# Midi2CV.net
KiCad netlist of a schematic drawn in EAGLE
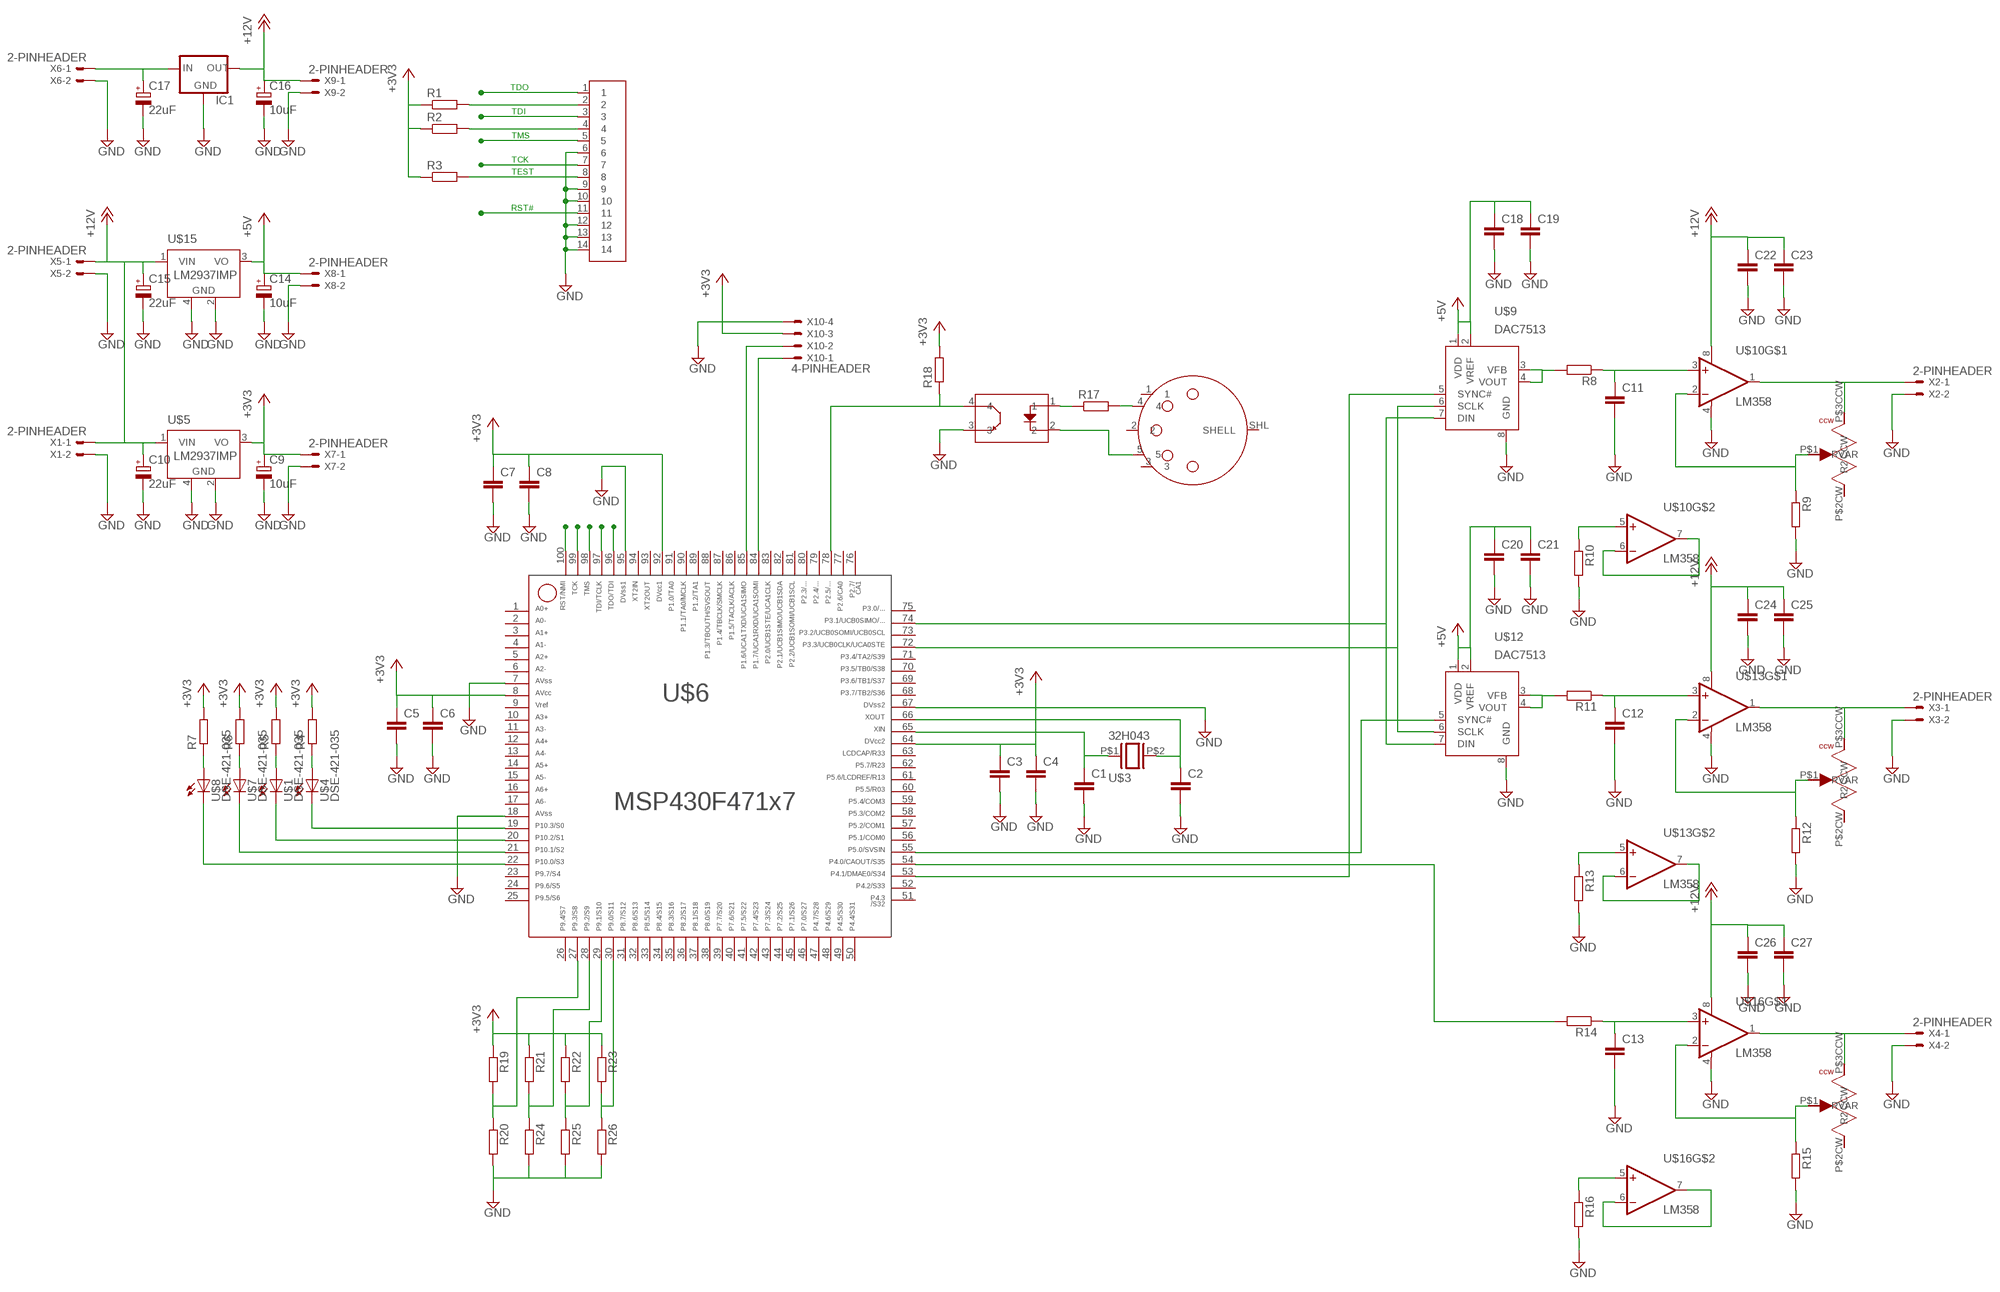
[diagram p0: schematic, sheet 1]

(export (version "E")
  (design (tool "Eeschema 10.0.6"))
  (components
    (comp (ref "C1")
      (value "C-EUC0402")
      (footprint "eagle-import:C0402")
      (libsource (lib "eagle-import") (part "C-EUC0402"))
    )
    (comp (ref "C2")
      (value "C-EUC0402")
      (footprint "eagle-import:C0402")
      (libsource (lib "eagle-import") (part "C-EUC0402"))
    )
    (comp (ref "C3")
      (value "C-EUC0402")
      (footprint "eagle-import:C0402")
      (libsource (lib "eagle-import") (part "C-EUC0402"))
    )
    (comp (ref "C4")
      (value "C-EUC0402")
      (footprint "eagle-import:C0402")
      (libsource (lib "eagle-import") (part "C-EUC0402"))
    )
    (comp (ref "C5")
      (value "C-EUC0402")
      (footprint "eagle-import:C0402")
      (libsource (lib "eagle-import") (part "C-EUC0402"))
    )
    (comp (ref "C6")
      (value "C-EUC0402")
      (footprint "eagle-import:C0402")
      (libsource (lib "eagle-import") (part "C-EUC0402"))
    )
    (comp (ref "C7")
      (value "C-EUC0402")
      (footprint "eagle-import:C0402")
      (libsource (lib "eagle-import") (part "C-EUC0402"))
    )
    (comp (ref "C8")
      (value "C-EUC0402")
      (footprint "eagle-import:C0402")
      (libsource (lib "eagle-import") (part "C-EUC0402"))
    )
    (comp (ref "C9")
      (value "10uF")
      (footprint "eagle-import:SMC_C")
      (libsource (lib "eagle-import") (part "CPOL-EUSMCC"))
    )
    (comp (ref "C10")
      (value "22uF")
      (footprint "eagle-import:SMC_D")
      (libsource (lib "eagle-import") (part "CPOL-EUSMCD"))
    )
    (comp (ref "C11")
      (value "C-EUC0402")
      (footprint "eagle-import:C0402")
      (libsource (lib "eagle-import") (part "C-EUC0402"))
    )
    (comp (ref "C12")
      (value "C-EUC0402")
      (footprint "eagle-import:C0402")
      (libsource (lib "eagle-import") (part "C-EUC0402"))
    )
    (comp (ref "C13")
      (value "C-EUC0402")
      (footprint "eagle-import:C0402")
      (libsource (lib "eagle-import") (part "C-EUC0402"))
    )
    (comp (ref "C14")
      (value "10uF")
      (footprint "eagle-import:SMC_C")
      (libsource (lib "eagle-import") (part "CPOL-EUSMCC"))
    )
    (comp (ref "C15")
      (value "22uF")
      (footprint "eagle-import:SMC_D")
      (libsource (lib "eagle-import") (part "CPOL-EUSMCD"))
    )
    (comp (ref "C16")
      (value "10uF")
      (footprint "eagle-import:SMC_C")
      (libsource (lib "eagle-import") (part "CPOL-EUSMCC"))
    )
    (comp (ref "C17")
      (value "22uF")
      (footprint "eagle-import:SMC_D")
      (libsource (lib "eagle-import") (part "CPOL-EUSMCD"))
    )
    (comp (ref "C18")
      (value "C-EUC0402")
      (footprint "eagle-import:C0402")
      (libsource (lib "eagle-import") (part "C-EUC0402"))
    )
    (comp (ref "C19")
      (value "C-EUC0402")
      (footprint "eagle-import:C0402")
      (libsource (lib "eagle-import") (part "C-EUC0402"))
    )
    (comp (ref "C20")
      (value "C-EUC0402")
      (footprint "eagle-import:C0402")
      (libsource (lib "eagle-import") (part "C-EUC0402"))
    )
    (comp (ref "C21")
      (value "C-EUC0402")
      (footprint "eagle-import:C0402")
      (libsource (lib "eagle-import") (part "C-EUC0402"))
    )
    (comp (ref "C22")
      (value "C-EUC0402")
      (footprint "eagle-import:C0402")
      (libsource (lib "eagle-import") (part "C-EUC0402"))
    )
    (comp (ref "C23")
      (value "C-EUC0402")
      (footprint "eagle-import:C0402")
      (libsource (lib "eagle-import") (part "C-EUC0402"))
    )
    (comp (ref "C24")
      (value "C-EUC0402")
      (footprint "eagle-import:C0402")
      (libsource (lib "eagle-import") (part "C-EUC0402"))
    )
    (comp (ref "C25")
      (value "C-EUC0402")
      (footprint "eagle-import:C0402")
      (libsource (lib "eagle-import") (part "C-EUC0402"))
    )
    (comp (ref "C26")
      (value "C-EUC0402")
      (footprint "eagle-import:C0402")
      (libsource (lib "eagle-import") (part "C-EUC0402"))
    )
    (comp (ref "C27")
      (value "C-EUC0402")
      (footprint "eagle-import:C0402")
      (libsource (lib "eagle-import") (part "C-EUC0402"))
    )
    (comp (ref "IC1")
      (value "78MXXS")
      (footprint "eagle-import:78MXXS")
      (libsource (lib "eagle-import") (part "78MXXS"))
    )
    (comp (ref "R1")
      (value "R-EU_R0402")
      (footprint "eagle-import:R0402")
      (libsource (lib "eagle-import") (part "R-EU_R0402"))
    )
    (comp (ref "R2")
      (value "R-EU_R0402")
      (footprint "eagle-import:R0402")
      (libsource (lib "eagle-import") (part "R-EU_R0402"))
    )
    (comp (ref "R3")
      (value "R-EU_R0402")
      (footprint "eagle-import:R0402")
      (libsource (lib "eagle-import") (part "R-EU_R0402"))
    )
    (comp (ref "R4")
      (value "R-EU_R0402")
      (footprint "eagle-import:R0402")
      (libsource (lib "eagle-import") (part "R-EU_R0402"))
    )
    (comp (ref "R5")
      (value "R-EU_R0402")
      (footprint "eagle-import:R0402")
      (libsource (lib "eagle-import") (part "R-EU_R0402"))
    )
    (comp (ref "R6")
      (value "R-EU_R0402")
      (footprint "eagle-import:R0402")
      (libsource (lib "eagle-import") (part "R-EU_R0402"))
    )
    (comp (ref "R7")
      (value "R-EU_R0402")
      (footprint "eagle-import:R0402")
      (libsource (lib "eagle-import") (part "R-EU_R0402"))
    )
    (comp (ref "R8")
      (value "R-EU_R0402")
      (footprint "eagle-import:R0402")
      (libsource (lib "eagle-import") (part "R-EU_R0402"))
    )
    (comp (ref "R9")
      (value "R-EU_R0402")
      (footprint "eagle-import:R0402")
      (libsource (lib "eagle-import") (part "R-EU_R0402"))
    )
    (comp (ref "R10")
      (value "R-EU_R0402")
      (footprint "eagle-import:R0402")
      (libsource (lib "eagle-import") (part "R-EU_R0402"))
    )
    (comp (ref "R11")
      (value "R-EU_R0402")
      (footprint "eagle-import:R0402")
      (libsource (lib "eagle-import") (part "R-EU_R0402"))
    )
    (comp (ref "R12")
      (value "R-EU_R0402")
      (footprint "eagle-import:R0402")
      (libsource (lib "eagle-import") (part "R-EU_R0402"))
    )
    (comp (ref "R13")
      (value "R-EU_R0402")
      (footprint "eagle-import:R0402")
      (libsource (lib "eagle-import") (part "R-EU_R0402"))
    )
    (comp (ref "R14")
      (value "R-EU_R0402")
      (footprint "eagle-import:R0402")
      (libsource (lib "eagle-import") (part "R-EU_R0402"))
    )
    (comp (ref "R15")
      (value "R-EU_R0402")
      (footprint "eagle-import:R0402")
      (libsource (lib "eagle-import") (part "R-EU_R0402"))
    )
    (comp (ref "R16")
      (value "R-EU_R0402")
      (footprint "eagle-import:R0402")
      (libsource (lib "eagle-import") (part "R-EU_R0402"))
    )
    (comp (ref "R17")
      (value "R-EU_R1206")
      (footprint "eagle-import:R1206")
      (libsource (lib "eagle-import") (part "R-EU_R1206"))
    )
    (comp (ref "R18")
      (value "R-EU_R1206")
      (footprint "eagle-import:R1206")
      (libsource (lib "eagle-import") (part "R-EU_R1206"))
    )
    (comp (ref "R19")
      (value "R-EU_R0402")
      (footprint "eagle-import:R0402")
      (libsource (lib "eagle-import") (part "R-EU_R0402"))
    )
    (comp (ref "R20")
      (value "R-EU_R0402")
      (footprint "eagle-import:R0402")
      (libsource (lib "eagle-import") (part "R-EU_R0402"))
    )
    (comp (ref "R21")
      (value "R-EU_R0402")
      (footprint "eagle-import:R0402")
      (libsource (lib "eagle-import") (part "R-EU_R0402"))
    )
    (comp (ref "R22")
      (value "R-EU_R0402")
      (footprint "eagle-import:R0402")
      (libsource (lib "eagle-import") (part "R-EU_R0402"))
    )
    (comp (ref "R23")
      (value "R-EU_R0402")
      (footprint "eagle-import:R0402")
      (libsource (lib "eagle-import") (part "R-EU_R0402"))
    )
    (comp (ref "R24")
      (value "R-EU_R0402")
      (footprint "eagle-import:R0402")
      (libsource (lib "eagle-import") (part "R-EU_R0402"))
    )
    (comp (ref "R25")
      (value "R-EU_R0402")
      (footprint "eagle-import:R0402")
      (libsource (lib "eagle-import") (part "R-EU_R0402"))
    )
    (comp (ref "R26")
      (value "R-EU_R0402")
      (footprint "eagle-import:R0402")
      (libsource (lib "eagle-import") (part "R-EU_R0402"))
    )
    (comp (ref "U$1")
      (value "DSE-421-035")
      (footprint "eagle-import:2432")
      (libsource (lib "eagle-import") (part "DSE-421-035"))
    )
    (comp (ref "U$2")
      (value "2X7SMD_HEADER")
      (footprint "eagle-import:2X14SMDPADS")
      (libsource (lib "eagle-import") (part "2X7SMD_HEADER"))
    )
    (comp (ref "U$3")
      (value "32H043")
      (footprint "eagle-import:XTAL-SMALL-4")
      (libsource (lib "eagle-import") (part "32H043"))
    )
    (comp (ref "U$4")
      (value "DSE-421-035")
      (footprint "eagle-import:2432")
      (libsource (lib "eagle-import") (part "DSE-421-035"))
    )
    (comp (ref "U$5")
      (value "LM2937IMP")
      (footprint "eagle-import:SOT223")
      (libsource (lib "eagle-import") (part "LM2937IMP"))
    )
    (comp (ref "U$6")
      (value "F471X7---PZ100")
      (footprint "eagle-import:PZ100")
      (libsource (lib "eagle-import") (part "F471X7---PZ100"))
    )
    (comp (ref "U$7")
      (value "DSE-421-035")
      (footprint "eagle-import:2432")
      (libsource (lib "eagle-import") (part "DSE-421-035"))
    )
    (comp (ref "U$8")
      (value "DSE-421-035")
      (footprint "eagle-import:2432")
      (libsource (lib "eagle-import") (part "DSE-421-035"))
    )
    (comp (ref "U$9")
      (value "DAC7513")
      (footprint "eagle-import:MSOP08")
      (libsource (lib "eagle-import") (part "DAC7513"))
    )
    (comp (ref "U$10")
      (value "LM358")
      (footprint "eagle-import:SO08")
      (libsource (lib "eagle-import") (part "LM358"))
    )
    (comp (ref "U$11")
      (value "SMD-POT")
      (footprint "eagle-import:POT_PADS")
      (libsource (lib "eagle-import") (part "SMD-POT"))
    )
    (comp (ref "U$12")
      (value "DAC7513")
      (footprint "eagle-import:MSOP08")
      (libsource (lib "eagle-import") (part "DAC7513"))
    )
    (comp (ref "U$13")
      (value "LM358")
      (footprint "eagle-import:SO08")
      (libsource (lib "eagle-import") (part "LM358"))
    )
    (comp (ref "U$14")
      (value "SMD-POT")
      (footprint "eagle-import:POT_PADS")
      (libsource (lib "eagle-import") (part "SMD-POT"))
    )
    (comp (ref "U$15")
      (value "LM2937IMP")
      (footprint "eagle-import:SOT223")
      (libsource (lib "eagle-import") (part "LM2937IMP"))
    )
    (comp (ref "U$16")
      (value "LM358")
      (footprint "eagle-import:SO08")
      (libsource (lib "eagle-import") (part "LM358"))
    )
    (comp (ref "U$17")
      (value "SMD-POT")
      (footprint "eagle-import:POT_PADS")
      (libsource (lib "eagle-import") (part "SMD-POT"))
    )
    (comp (ref "U$19")
      (value "F2801A")
      (footprint "eagle-import:LONG_TSOP")
      (libsource (lib "eagle-import") (part "F2801A"))
    )
    (comp (ref "U$20")
      (value "MIDI_VERT")
      (footprint "eagle-import:DIN-5_VERT")
      (libsource (lib "eagle-import") (part "MIDI_VERT"))
    )
    (comp (ref "X1")
      (value "2-PINHEADER")
      (footprint "eagle-import:22-23-2021")
      (fields (field (name "MF") "MOLEX") (field (name "MPN") "22-23-2021"))
      (libsource (lib "eagle-import") (part "2-PINHEADER"))
    )
    (comp (ref "X2")
      (value "2-PINHEADER")
      (footprint "eagle-import:22-23-2021")
      (fields (field (name "MF") "MOLEX") (field (name "MPN") "22-23-2021"))
      (libsource (lib "eagle-import") (part "2-PINHEADER"))
    )
    (comp (ref "X3")
      (value "2-PINHEADER")
      (footprint "eagle-import:22-23-2021")
      (fields (field (name "MF") "MOLEX") (field (name "MPN") "22-23-2021"))
      (libsource (lib "eagle-import") (part "2-PINHEADER"))
    )
    (comp (ref "X4")
      (value "2-PINHEADER")
      (footprint "eagle-import:22-23-2021")
      (fields (field (name "MF") "MOLEX") (field (name "MPN") "22-23-2021"))
      (libsource (lib "eagle-import") (part "2-PINHEADER"))
    )
    (comp (ref "X5")
      (value "2-PINHEADER")
      (footprint "eagle-import:22-23-2021")
      (fields (field (name "MF") "MOLEX") (field (name "MPN") "22-23-2021"))
      (libsource (lib "eagle-import") (part "2-PINHEADER"))
    )
    (comp (ref "X6")
      (value "2-PINHEADER")
      (footprint "eagle-import:22-23-2021")
      (fields (field (name "MF") "MOLEX") (field (name "MPN") "22-23-2021"))
      (libsource (lib "eagle-import") (part "2-PINHEADER"))
    )
    (comp (ref "X7")
      (value "2-PINHEADER")
      (footprint "eagle-import:22-23-2021")
      (fields (field (name "MF") "MOLEX") (field (name "MPN") "22-23-2021"))
      (libsource (lib "eagle-import") (part "2-PINHEADER"))
    )
    (comp (ref "X8")
      (value "2-PINHEADER")
      (footprint "eagle-import:22-23-2021")
      (fields (field (name "MF") "MOLEX") (field (name "MPN") "22-23-2021"))
      (libsource (lib "eagle-import") (part "2-PINHEADER"))
    )
    (comp (ref "X9")
      (value "2-PINHEADER")
      (footprint "eagle-import:22-23-2021")
      (fields (field (name "MF") "MOLEX") (field (name "MPN") "22-23-2021"))
      (libsource (lib "eagle-import") (part "2-PINHEADER"))
    )
    (comp (ref "X10")
      (value "4-PINHEADER")
      (footprint "eagle-import:22-23-2041")
      (fields (field (name "MF") "MOLEX") (field (name "MPN") "22-23-2041"))
      (libsource (lib "eagle-import") (part "4-PINHEADER"))
    )
  )
  (nets
    (net (code "1") (name "+3V3") (class "Default")
      (node (ref "C3") (pin "1") (pinfunction "1_1") (pintype "passive"))
      (node (ref "C4") (pin "1") (pinfunction "1_1") (pintype "passive"))
      (node (ref "C5") (pin "1") (pinfunction "1_1") (pintype "passive"))
      (node (ref "C6") (pin "1") (pinfunction "1_1") (pintype "passive"))
      (node (ref "C7") (pin "1") (pinfunction "1_1") (pintype "passive"))
      (node (ref "C8") (pin "1") (pinfunction "1_1") (pintype "passive"))
      (node (ref "C9") (pin "+") (pinfunction "+_+") (pintype "passive"))
      (node (ref "R1") (pin "1") (pinfunction "1_1") (pintype "passive"))
      (node (ref "R18") (pin "2") (pinfunction "2_2") (pintype "passive"))
      (node (ref "R19") (pin "1") (pinfunction "1_1") (pintype "passive"))
      (node (ref "R2") (pin "1") (pinfunction "1_1") (pintype "passive"))
      (node (ref "R21") (pin "1") (pinfunction "1_1") (pintype "passive"))
      (node (ref "R22") (pin "1") (pinfunction "1_1") (pintype "passive"))
      (node (ref "R23") (pin "1") (pinfunction "1_1") (pintype "passive"))
      (node (ref "R3") (pin "1") (pinfunction "1_1") (pintype "passive"))
      (node (ref "R4") (pin "2") (pinfunction "2_2") (pintype "passive"))
      (node (ref "R5") (pin "2") (pinfunction "2_2") (pintype "passive"))
      (node (ref "R6") (pin "2") (pinfunction "2_2") (pintype "passive"))
      (node (ref "R7") (pin "2") (pinfunction "2_2") (pintype "passive"))
      (node (ref "U$5") (pin "3") (pinfunction "VO_3") (pintype "passive"))
      (node (ref "U$6") (pin "64") (pinfunction "64_64") (pintype "power_in"))
      (node (ref "U$6") (pin "8") (pinfunction "8_8") (pintype "input"))
      (node (ref "U$6") (pin "92") (pinfunction "92_92") (pintype "power_in"))
      (node (ref "X10") (pin "3") (pinfunction "S_3") (pintype "passive"))
      (node (ref "X7") (pin "1") (pinfunction "S_1") (pintype "passive"))
    )
    (net (code "2") (name "+5V") (class "Default")
      (node (ref "C14") (pin "+") (pinfunction "+_+") (pintype "passive"))
      (node (ref "C18") (pin "1") (pinfunction "1_1") (pintype "passive"))
      (node (ref "C19") (pin "1") (pinfunction "1_1") (pintype "passive"))
      (node (ref "C20") (pin "1") (pinfunction "1_1") (pintype "passive"))
      (node (ref "C21") (pin "1") (pinfunction "1_1") (pintype "passive"))
      (node (ref "U$12") (pin "1") (pinfunction "VDD_1") (pintype "bidirectional"))
      (node (ref "U$12") (pin "2") (pinfunction "VREF_2") (pintype "bidirectional"))
      (node (ref "U$15") (pin "3") (pinfunction "VO_3") (pintype "passive"))
      (node (ref "U$9") (pin "1") (pinfunction "VDD_1") (pintype "bidirectional"))
      (node (ref "U$9") (pin "2") (pinfunction "VREF_2") (pintype "bidirectional"))
      (node (ref "X8") (pin "1") (pinfunction "S_1") (pintype "passive"))
    )
    (net (code "3") (name "+12V") (class "Default")
      (node (ref "C10") (pin "+") (pinfunction "+_+") (pintype "passive"))
      (node (ref "C15") (pin "+") (pinfunction "+_+") (pintype "passive"))
      (node (ref "C16") (pin "+") (pinfunction "+_+") (pintype "passive"))
      (node (ref "C22") (pin "1") (pinfunction "1_1") (pintype "passive"))
      (node (ref "C23") (pin "1") (pinfunction "1_1") (pintype "passive"))
      (node (ref "C24") (pin "1") (pinfunction "1_1") (pintype "passive"))
      (node (ref "C25") (pin "1") (pinfunction "1_1") (pintype "passive"))
      (node (ref "C26") (pin "1") (pinfunction "1_1") (pintype "passive"))
      (node (ref "C27") (pin "1") (pinfunction "1_1") (pintype "passive"))
      (node (ref "IC1") (pin "OUT") (pinfunction "OUT_OUT") (pintype "passive"))
      (node (ref "U$10") (pin "8") (pinfunction "V+_8") (pintype "power_in"))
      (node (ref "U$13") (pin "8") (pinfunction "V+_8") (pintype "power_in"))
      (node (ref "U$15") (pin "1") (pinfunction "VIN_1") (pintype "input"))
      (node (ref "U$16") (pin "8") (pinfunction "V+_8") (pintype "power_in"))
      (node (ref "U$5") (pin "1") (pinfunction "VIN_1") (pintype "input"))
      (node (ref "X1") (pin "1") (pinfunction "S_1") (pintype "passive"))
      (node (ref "X5") (pin "1") (pinfunction "S_1") (pintype "passive"))
      (node (ref "X9") (pin "1") (pinfunction "S_1") (pintype "passive"))
    )
    (net (code "4") (name "/RST#") (class "Default")
      (node (ref "U$2") (pin "11") (pinfunction "11_11") (pintype "input"))
      (node (ref "U$6") (pin "100") (pinfunction "100_100") (pintype "input"))
    )
    (net (code "5") (name "/TCK") (class "Default")
      (node (ref "U$2") (pin "7") (pinfunction "7_7") (pintype "input"))
      (node (ref "U$6") (pin "99") (pinfunction "99_99") (pintype "input"))
    )
    (net (code "6") (name "/TDI") (class "Default")
      (node (ref "U$2") (pin "3") (pinfunction "3_3") (pintype "input"))
      (node (ref "U$6") (pin "97") (pinfunction "97_97") (pintype "input"))
    )
    (net (code "7") (name "/TDO") (class "Default")
      (node (ref "U$2") (pin "1") (pinfunction "1_1") (pintype "input"))
      (node (ref "U$6") (pin "96") (pinfunction "96_96") (pintype "bidirectional"))
    )
    (net (code "8") (name "/TMS") (class "Default")
      (node (ref "U$2") (pin "5") (pinfunction "5_5") (pintype "input"))
      (node (ref "U$6") (pin "98") (pinfunction "98_98") (pintype "input"))
    )
    (net (code "9") (name "GND") (class "Default")
      (node (ref "C1") (pin "2") (pinfunction "2_2") (pintype "passive"))
      (node (ref "C10") (pin "-") (pinfunction "-_-") (pintype "passive"))
      (node (ref "C11") (pin "2") (pinfunction "2_2") (pintype "passive"))
      (node (ref "C12") (pin "2") (pinfunction "2_2") (pintype "passive"))
      (node (ref "C13") (pin "2") (pinfunction "2_2") (pintype "passive"))
      (node (ref "C14") (pin "-") (pinfunction "-_-") (pintype "passive"))
      (node (ref "C15") (pin "-") (pinfunction "-_-") (pintype "passive"))
      (node (ref "C16") (pin "-") (pinfunction "-_-") (pintype "passive"))
      (node (ref "C17") (pin "-") (pinfunction "-_-") (pintype "passive"))
      (node (ref "C18") (pin "2") (pinfunction "2_2") (pintype "passive"))
      (node (ref "C19") (pin "2") (pinfunction "2_2") (pintype "passive"))
      (node (ref "C2") (pin "2") (pinfunction "2_2") (pintype "passive"))
      (node (ref "C20") (pin "2") (pinfunction "2_2") (pintype "passive"))
      (node (ref "C21") (pin "2") (pinfunction "2_2") (pintype "passive"))
      (node (ref "C22") (pin "2") (pinfunction "2_2") (pintype "passive"))
      (node (ref "C23") (pin "2") (pinfunction "2_2") (pintype "passive"))
      (node (ref "C24") (pin "2") (pinfunction "2_2") (pintype "passive"))
      (node (ref "C25") (pin "2") (pinfunction "2_2") (pintype "passive"))
      (node (ref "C26") (pin "2") (pinfunction "2_2") (pintype "passive"))
      (node (ref "C27") (pin "2") (pinfunction "2_2") (pintype "passive"))
      (node (ref "C3") (pin "2") (pinfunction "2_2") (pintype "passive"))
      (node (ref "C4") (pin "2") (pinfunction "2_2") (pintype "passive"))
      (node (ref "C5") (pin "2") (pinfunction "2_2") (pintype "passive"))
      (node (ref "C6") (pin "2") (pinfunction "2_2") (pintype "passive"))
      (node (ref "C7") (pin "2") (pinfunction "2_2") (pintype "passive"))
      (node (ref "C8") (pin "2") (pinfunction "2_2") (pintype "passive"))
      (node (ref "C9") (pin "-") (pinfunction "-_-") (pintype "passive"))
      (node (ref "IC1") (pin "GND") (pinfunction "GND_GND") (pintype "input"))
      (node (ref "R10") (pin "2") (pinfunction "2_2") (pintype "passive"))
      (node (ref "R12") (pin "2") (pinfunction "2_2") (pintype "passive"))
      (node (ref "R13") (pin "2") (pinfunction "2_2") (pintype "passive"))
      (node (ref "R15") (pin "2") (pinfunction "2_2") (pintype "passive"))
      (node (ref "R16") (pin "2") (pinfunction "2_2") (pintype "passive"))
      (node (ref "R20") (pin "2") (pinfunction "2_2") (pintype "passive"))
      (node (ref "R24") (pin "2") (pinfunction "2_2") (pintype "passive"))
      (node (ref "R25") (pin "2") (pinfunction "2_2") (pintype "passive"))
      (node (ref "R26") (pin "2") (pinfunction "2_2") (pintype "passive"))
      (node (ref "R9") (pin "2") (pinfunction "2_2") (pintype "passive"))
      (node (ref "U$10") (pin "4") (pinfunction "V-_4") (pintype "power_in"))
      (node (ref "U$12") (pin "8") (pinfunction "GND_8") (pintype "bidirectional"))
      (node (ref "U$13") (pin "4") (pinfunction "V-_4") (pintype "power_in"))
      (node (ref "U$15") (pin "2") (pinfunction "GND_2") (pintype "passive"))
      (node (ref "U$15") (pin "4") (pinfunction "GND_4") (pintype "passive"))
      (node (ref "U$16") (pin "4") (pinfunction "V-_4") (pintype "power_in"))
      (node (ref "U$19") (pin "3") (pinfunction "3_3") (pintype "bidirectional"))
      (node (ref "U$2") (pin "10") (pinfunction "10_10") (pintype "input"))
      (node (ref "U$2") (pin "12") (pinfunction "12_12") (pintype "input"))
      (node (ref "U$2") (pin "13") (pinfunction "13_13") (pintype "input"))
      (node (ref "U$2") (pin "14") (pinfunction "14_14") (pintype "input"))
      (node (ref "U$2") (pin "6") (pinfunction "6_6") (pintype "input"))
      (node (ref "U$2") (pin "9") (pinfunction "9_9") (pintype "input"))
      (node (ref "U$5") (pin "2") (pinfunction "GND_2") (pintype "passive"))
      (node (ref "U$5") (pin "4") (pinfunction "GND_4") (pintype "passive"))
      (node (ref "U$6") (pin "18") (pinfunction "18_18") (pintype "power_in"))
      (node (ref "U$6") (pin "67") (pinfunction "67_67") (pintype "power_in"))
      (node (ref "U$6") (pin "7") (pinfunction "7_7") (pintype "input"))
      (node (ref "U$6") (pin "95") (pinfunction "95_95") (pintype "power_in"))
      (node (ref "U$9") (pin "8") (pinfunction "GND_8") (pintype "bidirectional"))
      (node (ref "X1") (pin "2") (pinfunction "S_2") (pintype "passive"))
      (node (ref "X10") (pin "4") (pinfunction "S_4") (pintype "passive"))
      (node (ref "X2") (pin "2") (pinfunction "S_2") (pintype "passive"))
      (node (ref "X3") (pin "2") (pinfunction "S_2") (pintype "passive"))
      (node (ref "X4") (pin "2") (pinfunction "S_2") (pintype "passive"))
      (node (ref "X5") (pin "2") (pinfunction "S_2") (pintype "passive"))
      (node (ref "X6") (pin "2") (pinfunction "S_2") (pintype "passive"))
      (node (ref "X7") (pin "2") (pinfunction "S_2") (pintype "passive"))
      (node (ref "X8") (pin "2") (pinfunction "S_2") (pintype "passive"))
      (node (ref "X9") (pin "2") (pinfunction "S_2") (pintype "passive"))
    )
    (net (code "10") (name "Net-(R1-Pad2)") (class "Default")
      (node (ref "R1") (pin "2") (pinfunction "2_2") (pintype "passive"))
      (node (ref "U$2") (pin "2") (pinfunction "2_2") (pintype "input"))
    )
    (net (code "11") (name "Net-(R2-Pad2)") (class "Default")
      (node (ref "R2") (pin "2") (pinfunction "2_2") (pintype "passive"))
      (node (ref "U$2") (pin "4") (pinfunction "4_4") (pintype "input"))
    )
    (net (code "12") (name "Net-(R3-Pad2)") (class "Default")
      (node (ref "R3") (pin "2") (pinfunction "2_2") (pintype "passive"))
      (node (ref "U$2") (pin "8") (pinfunction "8_8") (pintype "input"))
    )
    (net (code "13") (name "Net-(R14-Pad2)") (class "Default")
      (node (ref "R14") (pin "2") (pinfunction "2_2") (pintype "passive"))
      (node (ref "U$6") (pin "54") (pinfunction "54_54") (pintype "bidirectional"))
    )
    (net (code "14") (name "Net-(R17-Pad1)") (class "Default")
      (node (ref "R17") (pin "1") (pinfunction "1_1") (pintype "passive"))
      (node (ref "U$19") (pin "1") (pinfunction "1_1") (pintype "bidirectional"))
    )
    (net (code "15") (name "Net-(R17-Pad2)") (class "Default")
      (node (ref "R17") (pin "2") (pinfunction "2_2") (pintype "passive"))
      (node (ref "U$20") (pin "4") (pinfunction "4_4") (pintype "input"))
    )
    (net (code "16") (name "Net-(R18-Pad1)") (class "Default")
      (node (ref "R18") (pin "1") (pinfunction "1_1") (pintype "passive"))
      (node (ref "U$19") (pin "4") (pinfunction "4_4") (pintype "bidirectional"))
      (node (ref "U$6") (pin "78") (pinfunction "78_78") (pintype "bidirectional"))
    )
    (net (code "17") (name "Net-(R19-Pad2)") (class "Default")
      (node (ref "R19") (pin "2") (pinfunction "2_2") (pintype "passive"))
      (node (ref "R20") (pin "1") (pinfunction "1_1") (pintype "passive"))
      (node (ref "U$6") (pin "27") (pinfunction "27_27") (pintype "bidirectional"))
    )
    (net (code "18") (name "Net-(R21-Pad2)") (class "Default")
      (node (ref "R21") (pin "2") (pinfunction "2_2") (pintype "passive"))
      (node (ref "R24") (pin "1") (pinfunction "1_1") (pintype "passive"))
      (node (ref "U$6") (pin "28") (pinfunction "28_28") (pintype "bidirectional"))
    )
    (net (code "19") (name "Net-(R22-Pad2)") (class "Default")
      (node (ref "R22") (pin "2") (pinfunction "2_2") (pintype "passive"))
      (node (ref "R25") (pin "1") (pinfunction "1_1") (pintype "passive"))
      (node (ref "U$6") (pin "29") (pinfunction "29_29") (pintype "bidirectional"))
    )
    (net (code "20") (name "Net-(R23-Pad2)") (class "Default")
      (node (ref "R23") (pin "2") (pinfunction "2_2") (pintype "passive"))
      (node (ref "R26") (pin "1") (pinfunction "1_1") (pintype "passive"))
      (node (ref "U$6") (pin "30") (pinfunction "30_30") (pintype "bidirectional"))
    )
    (net (code "21") (name "Net-(U$1-A)") (class "Default")
      (node (ref "R5") (pin "1") (pinfunction "1_1") (pintype "passive"))
      (node (ref "U$1") (pin "P$1") (pinfunction "A_P$1") (pintype "passive"))
    )
    (net (code "22") (name "Net-(U$1-C)") (class "Default")
      (node (ref "U$1") (pin "MARKED") (pinfunction "C_MARKED") (pintype "passive"))
      (node (ref "U$6") (pin "20") (pinfunction "20_20") (pintype "bidirectional"))
    )
    (net (code "23") (name "Net-(U$3-1)") (class "Default")
      (node (ref "C1") (pin "1") (pinfunction "1_1") (pintype "passive"))
      (node (ref "U$3") (pin "P$1") (pinfunction "1_P$1") (pintype "bidirectional"))
      (node (ref "U$6") (pin "65") (pinfunction "65_65") (pintype "input"))
    )
    (net (code "24") (name "Net-(U$3-2)") (class "Default")
      (node (ref "C2") (pin "1") (pinfunction "1_1") (pintype "passive"))
      (node (ref "U$3") (pin "P$2") (pinfunction "2_P$2") (pintype "bidirectional"))
      (node (ref "U$6") (pin "66") (pinfunction "66_66") (pintype "output"))
    )
    (net (code "25") (name "Net-(U$4-A)") (class "Default")
      (node (ref "R4") (pin "1") (pinfunction "1_1") (pintype "passive"))
      (node (ref "U$4") (pin "P$1") (pinfunction "A_P$1") (pintype "passive"))
    )
    (net (code "26") (name "Net-(U$4-C)") (class "Default")
      (node (ref "U$4") (pin "MARKED") (pinfunction "C_MARKED") (pintype "passive"))
      (node (ref "U$6") (pin "19") (pinfunction "19_19") (pintype "bidirectional"))
    )
    (net (code "27") (name "Net-(U$7-A)") (class "Default")
      (node (ref "R6") (pin "1") (pinfunction "1_1") (pintype "passive"))
      (node (ref "U$7") (pin "P$1") (pinfunction "A_P$1") (pintype "passive"))
    )
    (net (code "28") (name "Net-(U$7-C)") (class "Default")
      (node (ref "U$6") (pin "21") (pinfunction "21_21") (pintype "bidirectional"))
      (node (ref "U$7") (pin "MARKED") (pinfunction "C_MARKED") (pintype "passive"))
    )
    (net (code "29") (name "Net-(U$8-A)") (class "Default")
      (node (ref "R7") (pin "1") (pinfunction "1_1") (pintype "passive"))
      (node (ref "U$8") (pin "P$1") (pinfunction "A_P$1") (pintype "passive"))
    )
    (net (code "30") (name "Net-(U$8-C)") (class "Default")
      (node (ref "U$6") (pin "22") (pinfunction "22_22") (pintype "bidirectional"))
      (node (ref "U$8") (pin "MARKED") (pinfunction "C_MARKED") (pintype "passive"))
    )
    (net (code "31") (name "Net-(U$9-SYNC#)") (class "Default")
      (node (ref "U$6") (pin "53") (pinfunction "53_53") (pintype "bidirectional"))
      (node (ref "U$9") (pin "5") (pinfunction "SYNC#_5") (pintype "bidirectional"))
    )
    (net (code "32") (name "Net-(U$9-VFB)") (class "Default")
      (node (ref "R8") (pin "2") (pinfunction "2_2") (pintype "passive"))
      (node (ref "U$9") (pin "3") (pinfunction "VFB_3") (pintype "bidirectional"))
      (node (ref "U$9") (pin "4") (pinfunction "VOUT_4") (pintype "bidirectional"))
    )
    (net (code "33") (name "Net-(U$10A-+IN)") (class "Default")
      (node (ref "C11") (pin "1") (pinfunction "1_1") (pintype "passive"))
      (node (ref "R8") (pin "1") (pinfunction "1_1") (pintype "passive"))
      (node (ref "U$10") (pin "3") (pinfunction "+IN_3") (pintype "input"))
    )
    (net (code "34") (name "Net-(U$10A--IN)") (class "Default")
      (node (ref "R9") (pin "1") (pinfunction "1_1") (pintype "passive"))
      (node (ref "U$10") (pin "2") (pinfunction "-IN_2") (pintype "input"))
      (node (ref "U$11") (pin "P$1") (pinfunction "RVAR_P$1") (pintype "bidirectional"))
    )
    (net (code "35") (name "Net-(U$10A-OUT)") (class "Default")
      (node (ref "U$10") (pin "1") (pinfunction "OUT_1") (pintype "output"))
      (node (ref "U$11") (pin "P$3CCW") (pinfunction "CCW_P$3CCW") (pintype "bidirectional"))
      (node (ref "X2") (pin "1") (pinfunction "S_1") (pintype "passive"))
    )
    (net (code "36") (name "Net-(U$10B-+IN)") (class "Default")
      (node (ref "R10") (pin "1") (pinfunction "1_1") (pintype "passive"))
      (node (ref "U$10") (pin "5") (pinfunction "+IN_5") (pintype "input"))
    )
    (net (code "37") (name "Net-(U$10B--IN)") (class "Default")
      (node (ref "U$10") (pin "6") (pinfunction "-IN_6") (pintype "input"))
      (node (ref "U$10") (pin "7") (pinfunction "OUT_7") (pintype "output"))
    )
    (net (code "38") (name "Net-(U$12-DIN)") (class "Default")
      (node (ref "U$12") (pin "7") (pinfunction "DIN_7") (pintype "bidirectional"))
      (node (ref "U$6") (pin "74") (pinfunction "74_74") (pintype "bidirectional"))
      (node (ref "U$9") (pin "7") (pinfunction "DIN_7") (pintype "bidirectional"))
    )
    (net (code "39") (name "Net-(U$12-SCLK)") (class "Default")
      (node (ref "U$12") (pin "6") (pinfunction "SCLK_6") (pintype "bidirectional"))
      (node (ref "U$6") (pin "72") (pinfunction "72_72") (pintype "bidirectional"))
      (node (ref "U$9") (pin "6") (pinfunction "SCLK_6") (pintype "bidirectional"))
    )
    (net (code "40") (name "Net-(U$12-SYNC#)") (class "Default")
      (node (ref "U$12") (pin "5") (pinfunction "SYNC#_5") (pintype "bidirectional"))
      (node (ref "U$6") (pin "55") (pinfunction "55_55") (pintype "bidirectional"))
    )
    (net (code "41") (name "Net-(U$12-VFB)") (class "Default")
      (node (ref "R11") (pin "2") (pinfunction "2_2") (pintype "passive"))
      (node (ref "U$12") (pin "3") (pinfunction "VFB_3") (pintype "bidirectional"))
      (node (ref "U$12") (pin "4") (pinfunction "VOUT_4") (pintype "bidirectional"))
    )
    (net (code "42") (name "Net-(U$13A-+IN)") (class "Default")
      (node (ref "C12") (pin "1") (pinfunction "1_1") (pintype "passive"))
      (node (ref "R11") (pin "1") (pinfunction "1_1") (pintype "passive"))
      (node (ref "U$13") (pin "3") (pinfunction "+IN_3") (pintype "input"))
    )
    (net (code "43") (name "Net-(U$13A--IN)") (class "Default")
      (node (ref "R12") (pin "1") (pinfunction "1_1") (pintype "passive"))
      (node (ref "U$13") (pin "2") (pinfunction "-IN_2") (pintype "input"))
      (node (ref "U$14") (pin "P$1") (pinfunction "RVAR_P$1") (pintype "bidirectional"))
    )
    (net (code "44") (name "Net-(U$13A-OUT)") (class "Default")
      (node (ref "U$13") (pin "1") (pinfunction "OUT_1") (pintype "output"))
      (node (ref "U$14") (pin "P$3CCW") (pinfunction "CCW_P$3CCW") (pintype "bidirectional"))
      (node (ref "X3") (pin "1") (pinfunction "S_1") (pintype "passive"))
    )
    (net (code "45") (name "Net-(U$13B-+IN)") (class "Default")
      (node (ref "R13") (pin "1") (pinfunction "1_1") (pintype "passive"))
      (node (ref "U$13") (pin "5") (pinfunction "+IN_5") (pintype "input"))
    )
    (net (code "46") (name "Net-(U$13B--IN)") (class "Default")
      (node (ref "U$13") (pin "6") (pinfunction "-IN_6") (pintype "input"))
      (node (ref "U$13") (pin "7") (pinfunction "OUT_7") (pintype "output"))
    )
    (net (code "47") (name "Net-(U$16A-+IN)") (class "Default")
      (node (ref "C13") (pin "1") (pinfunction "1_1") (pintype "passive"))
      (node (ref "R14") (pin "1") (pinfunction "1_1") (pintype "passive"))
      (node (ref "U$16") (pin "3") (pinfunction "+IN_3") (pintype "input"))
    )
    (net (code "48") (name "Net-(U$16A--IN)") (class "Default")
      (node (ref "R15") (pin "1") (pinfunction "1_1") (pintype "passive"))
      (node (ref "U$16") (pin "2") (pinfunction "-IN_2") (pintype "input"))
      (node (ref "U$17") (pin "P$1") (pinfunction "RVAR_P$1") (pintype "bidirectional"))
    )
    (net (code "49") (name "Net-(U$16A-OUT)") (class "Default")
      (node (ref "U$16") (pin "1") (pinfunction "OUT_1") (pintype "output"))
      (node (ref "U$17") (pin "P$3CCW") (pinfunction "CCW_P$3CCW") (pintype "bidirectional"))
      (node (ref "X4") (pin "1") (pinfunction "S_1") (pintype "passive"))
    )
    (net (code "50") (name "Net-(U$16B-+IN)") (class "Default")
      (node (ref "R16") (pin "1") (pinfunction "1_1") (pintype "passive"))
      (node (ref "U$16") (pin "5") (pinfunction "+IN_5") (pintype "input"))
    )
    (net (code "51") (name "Net-(U$16B--IN)") (class "Default")
      (node (ref "U$16") (pin "6") (pinfunction "-IN_6") (pintype "input"))
      (node (ref "U$16") (pin "7") (pinfunction "OUT_7") (pintype "output"))
    )
    (net (code "52") (name "Net-(U$19-Pad2)") (class "Default")
      (node (ref "U$19") (pin "2") (pinfunction "2_2") (pintype "bidirectional"))
      (node (ref "U$20") (pin "5") (pinfunction "5_5") (pintype "input"))
    )
    (net (code "53") (name "Net-(X6A-S)") (class "Default")
      (node (ref "C17") (pin "+") (pinfunction "+_+") (pintype "passive"))
      (node (ref "IC1") (pin "IN") (pinfunction "IN_IN") (pintype "input"))
      (node (ref "X6") (pin "1") (pinfunction "S_1") (pintype "passive"))
    )
    (net (code "54") (name "Net-(X10A-S)") (class "Default")
      (node (ref "U$6") (pin "84") (pinfunction "84_84") (pintype "bidirectional"))
      (node (ref "X10") (pin "1") (pinfunction "S_1") (pintype "passive"))
    )
    (net (code "55") (name "Net-(X10B-S)") (class "Default")
      (node (ref "U$6") (pin "85") (pinfunction "85_85") (pintype "bidirectional"))
      (node (ref "X10") (pin "2") (pinfunction "S_2") (pintype "passive"))
    )
    (net (code "56") (name "unconnected-(U$6-Pad1)") (class "Default")
      (node (ref "U$6") (pin "1") (pinfunction "1_1") (pintype "input"))
    )
    (net (code "57") (name "unconnected-(U$6-Pad2)") (class "Default")
      (node (ref "U$6") (pin "2") (pinfunction "2_2") (pintype "input"))
    )
    (net (code "58") (name "unconnected-(U$6-Pad3)") (class "Default")
      (node (ref "U$6") (pin "3") (pinfunction "3_3") (pintype "input"))
    )
    (net (code "59") (name "unconnected-(U$6-Pad4)") (class "Default")
      (node (ref "U$6") (pin "4") (pinfunction "4_4") (pintype "input"))
    )
    (net (code "60") (name "unconnected-(U$6-Pad5)") (class "Default")
      (node (ref "U$6") (pin "5") (pinfunction "5_5") (pintype "input"))
    )
    (net (code "61") (name "unconnected-(U$6-Pad6)") (class "Default")
      (node (ref "U$6") (pin "6") (pinfunction "6_6") (pintype "input"))
    )
    (net (code "62") (name "unconnected-(U$6-Pad9)") (class "Default")
      (node (ref "U$6") (pin "9") (pinfunction "9_9") (pintype "bidirectional"))
    )
    (net (code "63") (name "unconnected-(U$6-Pad10)") (class "Default")
      (node (ref "U$6") (pin "10") (pinfunction "10_10") (pintype "input"))
    )
    (net (code "64") (name "unconnected-(U$6-Pad11)") (class "Default")
      (node (ref "U$6") (pin "11") (pinfunction "11_11") (pintype "input"))
    )
    (net (code "65") (name "unconnected-(U$6-Pad12)") (class "Default")
      (node (ref "U$6") (pin "12") (pinfunction "12_12") (pintype "input"))
    )
    (net (code "66") (name "unconnected-(U$6-Pad13)") (class "Default")
      (node (ref "U$6") (pin "13") (pinfunction "13_13") (pintype "input"))
    )
    (net (code "67") (name "unconnected-(U$6-Pad14)") (class "Default")
      (node (ref "U$6") (pin "14") (pinfunction "14_14") (pintype "input"))
    )
    (net (code "68") (name "unconnected-(U$6-Pad15)") (class "Default")
      (node (ref "U$6") (pin "15") (pinfunction "15_15") (pintype "input"))
    )
    (net (code "69") (name "unconnected-(U$6-Pad16)") (class "Default")
      (node (ref "U$6") (pin "16") (pinfunction "16_16") (pintype "input"))
    )
    (net (code "70") (name "unconnected-(U$6-Pad17)") (class "Default")
      (node (ref "U$6") (pin "17") (pinfunction "17_17") (pintype "input"))
    )
    (net (code "71") (name "unconnected-(U$6-Pad23)") (class "Default")
      (node (ref "U$6") (pin "23") (pinfunction "23_23") (pintype "bidirectional"))
    )
    (net (code "72") (name "unconnected-(U$6-Pad24)") (class "Default")
      (node (ref "U$6") (pin "24") (pinfunction "24_24") (pintype "bidirectional"))
    )
    (net (code "73") (name "unconnected-(U$6-Pad25)") (class "Default")
      (node (ref "U$6") (pin "25") (pinfunction "25_25") (pintype "bidirectional"))
    )
    (net (code "74") (name "unconnected-(U$6-Pad26)") (class "Default")
      (node (ref "U$6") (pin "26") (pinfunction "26_26") (pintype "bidirectional"))
    )
    (net (code "75") (name "unconnected-(U$6-Pad31)") (class "Default")
      (node (ref "U$6") (pin "31") (pinfunction "31_31") (pintype "bidirectional"))
    )
    (net (code "76") (name "unconnected-(U$6-Pad32)") (class "Default")
      (node (ref "U$6") (pin "32") (pinfunction "32_32") (pintype "bidirectional"))
    )
    (net (code "77") (name "unconnected-(U$6-Pad33)") (class "Default")
      (node (ref "U$6") (pin "33") (pinfunction "33_33") (pintype "bidirectional"))
    )
    (net (code "78") (name "unconnected-(U$6-Pad34)") (class "Default")
      (node (ref "U$6") (pin "34") (pinfunction "34_34") (pintype "bidirectional"))
    )
    (net (code "79") (name "unconnected-(U$6-Pad35)") (class "Default")
      (node (ref "U$6") (pin "35") (pinfunction "35_35") (pintype "bidirectional"))
    )
    (net (code "80") (name "unconnected-(U$6-Pad36)") (class "Default")
      (node (ref "U$6") (pin "36") (pinfunction "36_36") (pintype "bidirectional"))
    )
    (net (code "81") (name "unconnected-(U$6-Pad37)") (class "Default")
      (node (ref "U$6") (pin "37") (pinfunction "37_37") (pintype "bidirectional"))
    )
    (net (code "82") (name "unconnected-(U$6-Pad38)") (class "Default")
      (node (ref "U$6") (pin "38") (pinfunction "38_38") (pintype "bidirectional"))
    )
    (net (code "83") (name "unconnected-(U$6-Pad39)") (class "Default")
      (node (ref "U$6") (pin "39") (pinfunction "39_39") (pintype "bidirectional"))
    )
    (net (code "84") (name "unconnected-(U$6-Pad40)") (class "Default")
      (node (ref "U$6") (pin "40") (pinfunction "40_40") (pintype "bidirectional"))
    )
    (net (code "85") (name "unconnected-(U$6-Pad41)") (class "Default")
      (node (ref "U$6") (pin "41") (pinfunction "41_41") (pintype "bidirectional"))
    )
    (net (code "86") (name "unconnected-(U$6-Pad42)") (class "Default")
      (node (ref "U$6") (pin "42") (pinfunction "42_42") (pintype "bidirectional"))
    )
    (net (code "87") (name "unconnected-(U$6-Pad43)") (class "Default")
      (node (ref "U$6") (pin "43") (pinfunction "43_43") (pintype "bidirectional"))
    )
    (net (code "88") (name "unconnected-(U$6-Pad44)") (class "Default")
      (node (ref "U$6") (pin "44") (pinfunction "44_44") (pintype "bidirectional"))
    )
    (net (code "89") (name "unconnected-(U$6-Pad45)") (class "Default")
      (node (ref "U$6") (pin "45") (pinfunction "45_45") (pintype "bidirectional"))
    )
    (net (code "90") (name "unconnected-(U$6-Pad46)") (class "Default")
      (node (ref "U$6") (pin "46") (pinfunction "46_46") (pintype "bidirectional"))
    )
    (net (code "91") (name "unconnected-(U$6-Pad47)") (class "Default")
      (node (ref "U$6") (pin "47") (pinfunction "47_47") (pintype "bidirectional"))
    )
    (net (code "92") (name "unconnected-(U$6-Pad48)") (class "Default")
      (node (ref "U$6") (pin "48") (pinfunction "48_48") (pintype "bidirectional"))
    )
    (net (code "93") (name "unconnected-(U$6-Pad49)") (class "Default")
      (node (ref "U$6") (pin "49") (pinfunction "49_49") (pintype "bidirectional"))
    )
    (net (code "94") (name "unconnected-(U$6-Pad50)") (class "Default")
      (node (ref "U$6") (pin "50") (pinfunction "50_50") (pintype "bidirectional"))
    )
    (net (code "95") (name "unconnected-(U$6-Pad51)") (class "Default")
      (node (ref "U$6") (pin "51") (pinfunction "51_51") (pintype "bidirectional"))
    )
    (net (code "96") (name "unconnected-(U$6-Pad52)") (class "Default")
      (node (ref "U$6") (pin "52") (pinfunction "52_52") (pintype "bidirectional"))
    )
    (net (code "97") (name "unconnected-(U$6-Pad56)") (class "Default")
      (node (ref "U$6") (pin "56") (pinfunction "56_56") (pintype "bidirectional"))
    )
    (net (code "98") (name "unconnected-(U$6-Pad57)") (class "Default")
      (node (ref "U$6") (pin "57") (pinfunction "57_57") (pintype "bidirectional"))
    )
    (net (code "99") (name "unconnected-(U$6-Pad58)") (class "Default")
      (node (ref "U$6") (pin "58") (pinfunction "58_58") (pintype "bidirectional"))
    )
    (net (code "100") (name "unconnected-(U$6-Pad59)") (class "Default")
      (node (ref "U$6") (pin "59") (pinfunction "59_59") (pintype "bidirectional"))
    )
    (net (code "101") (name "unconnected-(U$6-Pad60)") (class "Default")
      (node (ref "U$6") (pin "60") (pinfunction "60_60") (pintype "bidirectional"))
    )
    (net (code "102") (name "unconnected-(U$6-Pad61)") (class "Default")
      (node (ref "U$6") (pin "61") (pinfunction "61_61") (pintype "bidirectional"))
    )
    (net (code "103") (name "unconnected-(U$6-Pad62)") (class "Default")
      (node (ref "U$6") (pin "62") (pinfunction "62_62") (pintype "bidirectional"))
    )
    (net (code "104") (name "unconnected-(U$6-Pad63)") (class "Default")
      (node (ref "U$6") (pin "63") (pinfunction "63_63") (pintype "input"))
    )
    (net (code "105") (name "unconnected-(U$6-Pad68)") (class "Default")
      (node (ref "U$6") (pin "68") (pinfunction "68_68") (pintype "bidirectional"))
    )
    (net (code "106") (name "unconnected-(U$6-Pad69)") (class "Default")
      (node (ref "U$6") (pin "69") (pinfunction "69_69") (pintype "bidirectional"))
    )
    (net (code "107") (name "unconnected-(U$6-Pad70)") (class "Default")
      (node (ref "U$6") (pin "70") (pinfunction "70_70") (pintype "bidirectional"))
    )
    (net (code "108") (name "unconnected-(U$6-Pad71)") (class "Default")
      (node (ref "U$6") (pin "71") (pinfunction "71_71") (pintype "bidirectional"))
    )
    (net (code "109") (name "unconnected-(U$6-Pad73)") (class "Default")
      (node (ref "U$6") (pin "73") (pinfunction "73_73") (pintype "bidirectional"))
    )
    (net (code "110") (name "unconnected-(U$6-Pad75)") (class "Default")
      (node (ref "U$6") (pin "75") (pinfunction "75_75") (pintype "bidirectional"))
    )
    (net (code "111") (name "unconnected-(U$6-Pad76)") (class "Default")
      (node (ref "U$6") (pin "76") (pinfunction "76_76") (pintype "bidirectional"))
    )
    (net (code "112") (name "unconnected-(U$6-Pad77)") (class "Default")
      (node (ref "U$6") (pin "77") (pinfunction "77_77") (pintype "bidirectional"))
    )
    (net (code "113") (name "unconnected-(U$6-Pad79)") (class "Default")
      (node (ref "U$6") (pin "79") (pinfunction "79_79") (pintype "bidirectional"))
    )
    (net (code "114") (name "unconnected-(U$6-Pad80)") (class "Default")
      (node (ref "U$6") (pin "80") (pinfunction "80_80") (pintype "bidirectional"))
    )
    (net (code "115") (name "unconnected-(U$6-Pad81)") (class "Default")
      (node (ref "U$6") (pin "81") (pinfunction "81_81") (pintype "bidirectional"))
    )
    (net (code "116") (name "unconnected-(U$6-Pad82)") (class "Default")
      (node (ref "U$6") (pin "82") (pinfunction "82_82") (pintype "bidirectional"))
    )
    (net (code "117") (name "unconnected-(U$6-Pad83)") (class "Default")
      (node (ref "U$6") (pin "83") (pinfunction "83_83") (pintype "bidirectional"))
    )
    (net (code "118") (name "unconnected-(U$6-Pad86)") (class "Default")
      (node (ref "U$6") (pin "86") (pinfunction "86_86") (pintype "bidirectional"))
    )
    (net (code "119") (name "unconnected-(U$6-Pad87)") (class "Default")
      (node (ref "U$6") (pin "87") (pinfunction "87_87") (pintype "bidirectional"))
    )
    (net (code "120") (name "unconnected-(U$6-Pad88)") (class "Default")
      (node (ref "U$6") (pin "88") (pinfunction "88_88") (pintype "bidirectional"))
    )
    (net (code "121") (name "unconnected-(U$6-Pad89)") (class "Default")
      (node (ref "U$6") (pin "89") (pinfunction "89_89") (pintype "bidirectional"))
    )
    (net (code "122") (name "unconnected-(U$6-Pad90)") (class "Default")
      (node (ref "U$6") (pin "90") (pinfunction "90_90") (pintype "bidirectional"))
    )
    (net (code "123") (name "unconnected-(U$6-Pad91)") (class "Default")
      (node (ref "U$6") (pin "91") (pinfunction "91_91") (pintype "bidirectional"))
    )
    (net (code "124") (name "unconnected-(U$6-Pad93)") (class "Default")
      (node (ref "U$6") (pin "93") (pinfunction "93_93") (pintype "output"))
    )
    (net (code "125") (name "unconnected-(U$6-Pad94)") (class "Default")
      (node (ref "U$6") (pin "94") (pinfunction "94_94") (pintype "input"))
    )
    (net (code "126") (name "unconnected-(U$11-R2-PadP$2CW)") (class "Default")
      (node (ref "U$11") (pin "P$2CW") (pinfunction "R2_P$2CW") (pintype "bidirectional"))
    )
    (net (code "127") (name "unconnected-(U$14-R2-PadP$2CW)") (class "Default")
      (node (ref "U$14") (pin "P$2CW") (pinfunction "R2_P$2CW") (pintype "bidirectional"))
    )
    (net (code "128") (name "unconnected-(U$17-R2-PadP$2CW)") (class "Default")
      (node (ref "U$17") (pin "P$2CW") (pinfunction "R2_P$2CW") (pintype "bidirectional"))
    )
    (net (code "129") (name "unconnected-(U$20-Pad1)") (class "Default")
      (node (ref "U$20") (pin "1") (pinfunction "1_1") (pintype "input"))
    )
    (net (code "130") (name "unconnected-(U$20-Pad2)") (class "Default")
      (node (ref "U$20") (pin "2") (pinfunction "2_2") (pintype "input"))
    )
    (net (code "131") (name "unconnected-(U$20-Pad3)") (class "Default")
      (node (ref "U$20") (pin "3") (pinfunction "3_3") (pintype "input"))
    )
    (net (code "132") (name "unconnected-(U$20-SHELL-PadSHL)") (class "Default")
      (node (ref "U$20") (pin "SHL") (pinfunction "SHELL_SHL") (pintype "input"))
    )
  )
)
